# Accelerometer.net
KiCad netlist of a schematic drawn in Altium Designer
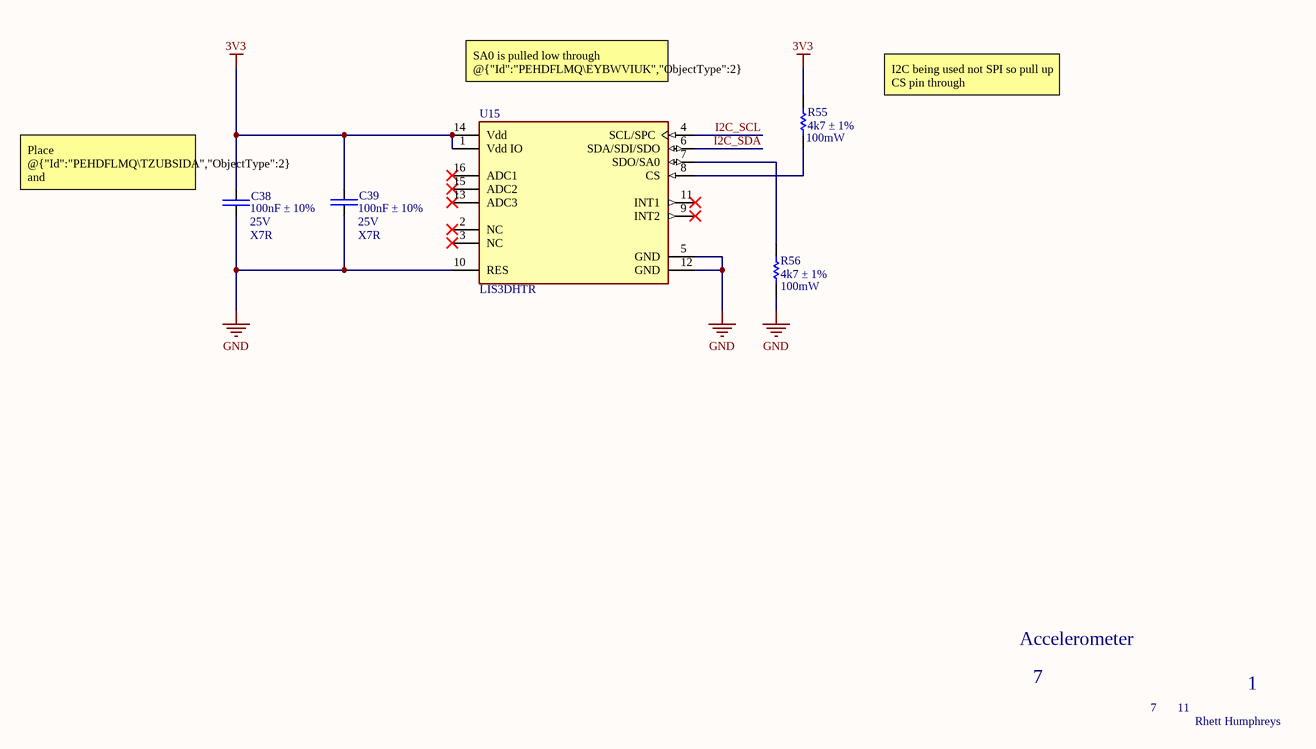
[diagram p0: Accelerometer.SchDoc]

(export (version "E")
  (design (tool "Eeschema 10.0.6"))
  (components
    (comp (ref "C38")
      (value "100nF ± 10%")
      (footprint "CAP-0603")
      (description "Capacitor chip unpolarized. 0603")
      (libsource (lib "Master") (part "CAP-0603"))
    )
    (comp (ref "C39")
      (value "100nF ± 10%")
      (footprint "CAP-0603")
      (description "Capacitor chip unpolarized. 0603")
      (libsource (lib "Master") (part "CAP-0603"))
    )
    (comp (ref "R55")
      (value "4k7 ± 1%")
      (footprint "RESC1609X50X30NL8T20")
      (description "Chip Resistor, 10 KOhm, +/- 1%, 100 mW, -55 to 155 degC, 0603 (1608 Metric), RoHS, Tape and Reel")
      (fields (field (name "MANUFACTURER") "Vishay Semiconductor"))
      (libsource (lib "Altium Content Vault") (part "RES-2"))
    )
    (comp (ref "R56")
      (value "4k7 ± 1%")
      (footprint "RESC1609X50X30NL8T20")
      (description "Chip Resistor, 10 KOhm, +/- 1%, 100 mW, -55 to 155 degC, 0603 (1608 Metric), RoHS, Tape and Reel")
      (fields (field (name "MANUFACTURER") "Vishay Semiconductor"))
      (libsource (lib "Altium Content Vault") (part "RES-2"))
    )
    (comp (ref "U15")
      (value "LIS3DHTR")
      (footprint "FP-LGA-16-7983231-MFG")
      (description "ACCEL 2-16G I2C/SPI 16LGA")
      (libsource (lib "Altium Content Vault") (part "1e4772b22d749da4b53766bc623c8dd"))
    )
  )
  (nets
    (net (code "1") (name "/I2C_SCL") (class "Default")
      (node (ref "U15") (pin "4") (pinfunction "SCL/SPC_4") (pintype "input"))
    )
    (net (code "2") (name "/I2C_SDA") (class "Default")
      (node (ref "U15") (pin "6") (pinfunction "SDA/SDI/SDO_6") (pintype "bidirectional"))
    )
    (net (code "3") (name "3V3") (class "Default")
      (node (ref "C38") (pin "2") (pintype "passive"))
      (node (ref "C39") (pin "2") (pintype "passive"))
      (node (ref "R55") (pin "2") (pinfunction "2_2") (pintype "passive"))
      (node (ref "U15") (pin "1") (pinfunction "Vdd_IO_1") (pintype "power_in"))
      (node (ref "U15") (pin "14") (pinfunction "Vdd_14") (pintype "power_in"))
    )
    (net (code "4") (name "GND") (class "Default")
      (node (ref "C38") (pin "1") (pintype "passive"))
      (node (ref "C39") (pin "1") (pintype "passive"))
      (node (ref "R56") (pin "1") (pinfunction "1_1") (pintype "passive"))
      (node (ref "U15") (pin "10") (pinfunction "RES_10") (pintype "passive"))
      (node (ref "U15") (pin "12") (pinfunction "GND_12") (pintype "power_in"))
      (node (ref "U15") (pin "5") (pinfunction "GND_5") (pintype "power_in"))
    )
    (net (code "5") (name "Net-(U15-CS)") (class "Default")
      (node (ref "R55") (pin "1") (pinfunction "1_1") (pintype "passive"))
      (node (ref "U15") (pin "8") (pinfunction "CS_8") (pintype "input"))
    )
    (net (code "6") (name "Net-(U15-SDO{slash}SA0)") (class "Default")
      (node (ref "R56") (pin "2") (pinfunction "2_2") (pintype "passive"))
      (node (ref "U15") (pin "7") (pinfunction "SDO/SA0_7") (pintype "bidirectional"))
    )
    (net (code "7") (name "unconnected-(U15-ADC1-Pad16)") (class "Default")
      (node (ref "U15") (pin "16") (pinfunction "ADC1_16") (pintype "passive+no_connect"))
    )
    (net (code "8") (name "unconnected-(U15-ADC2-Pad15)") (class "Default")
      (node (ref "U15") (pin "15") (pinfunction "ADC2_15") (pintype "passive+no_connect"))
    )
    (net (code "9") (name "unconnected-(U15-ADC3-Pad13)") (class "Default")
      (node (ref "U15") (pin "13") (pinfunction "ADC3_13") (pintype "passive+no_connect"))
    )
    (net (code "10") (name "unconnected-(U15-INT1-Pad11)") (class "Default")
      (node (ref "U15") (pin "11") (pinfunction "INT1_11") (pintype "output+no_connect"))
    )
    (net (code "11") (name "unconnected-(U15-INT2-Pad9)") (class "Default")
      (node (ref "U15") (pin "9") (pinfunction "INT2_9") (pintype "output+no_connect"))
    )
    (net (code "12") (name "unconnected-(U15-NC-Pad2)") (class "Default")
      (node (ref "U15") (pin "2") (pinfunction "NC_2") (pintype "passive+no_connect"))
    )
    (net (code "13") (name "unconnected-(U15-NC-Pad3)") (class "Default")
      (node (ref "U15") (pin "3") (pinfunction "NC_3") (pintype "passive+no_connect"))
    )
  )
)
